# LTC3115_-_przetwornica_wiatrak.net
KiCad netlist of a schematic drawn in EAGLE
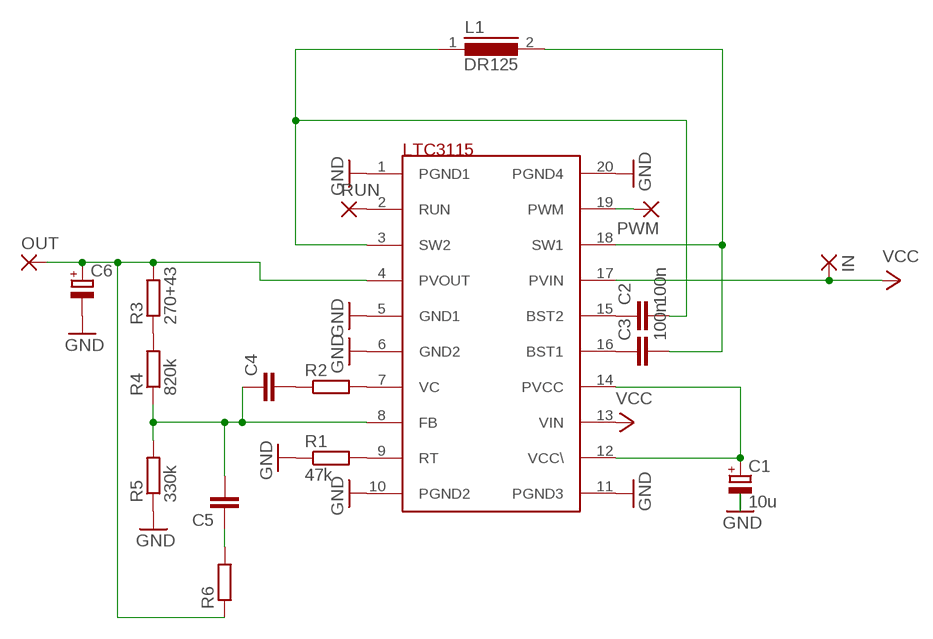
[diagram p0: schematic, sheet 1]

(export (version "E")
  (design (tool "Eeschema 10.0.6"))
  (components
    (comp (ref "C1")
      (value "10u")
      (footprint "eagle-import:E2,5-7")
      (libsource (lib "eagle-import") (part "CPOL-EUE2.5-7"))
    )
    (comp (ref "C2")
      (value "100n")
      (footprint "eagle-import:C0805")
      (libsource (lib "eagle-import") (part "C-EUC0805"))
    )
    (comp (ref "C3")
      (value "100n")
      (footprint "eagle-import:C0805")
      (libsource (lib "eagle-import") (part "C-EUC0805"))
    )
    (comp (ref "C4")
      (value "C-EUC0805")
      (footprint "eagle-import:C0805")
      (libsource (lib "eagle-import") (part "C-EUC0805"))
    )
    (comp (ref "C5")
      (value "C-EUC0805")
      (footprint "eagle-import:C0805")
      (libsource (lib "eagle-import") (part "C-EUC0805"))
    )
    (comp (ref "C6")
      (value "CPOL-EUE3.5-8")
      (footprint "eagle-import:E3,5-8")
      (libsource (lib "eagle-import") (part "CPOL-EUE3.5-8"))
    )
    (comp (ref "IN")
      (value "2,54/0,9")
      (footprint "eagle-import:2,54_0,9")
      (libsource (lib "eagle-import") (part "2,54/0,9"))
    )
    (comp (ref "L1")
      (value "DR125")
      (footprint "eagle-import:DR125")
      (libsource (lib "eagle-import") (part "DR125"))
    )
    (comp (ref "OUT")
      (value "2,54/0,9")
      (footprint "eagle-import:2,54_0,9")
      (libsource (lib "eagle-import") (part "2,54/0,9"))
    )
    (comp (ref "PWM")
      (value "2,54/0,9")
      (footprint "eagle-import:2,54_0,9")
      (libsource (lib "eagle-import") (part "2,54/0,9"))
    )
    (comp (ref "R1")
      (value "47k")
      (footprint "eagle-import:R0805")
      (libsource (lib "eagle-import") (part "R-EU_R0805"))
    )
    (comp (ref "R2")
      (value "R-EU_R0805")
      (footprint "eagle-import:R0805")
      (libsource (lib "eagle-import") (part "R-EU_R0805"))
    )
    (comp (ref "R3")
      (value "270+43")
      (footprint "eagle-import:R0805")
      (libsource (lib "eagle-import") (part "R-EU_R0805"))
    )
    (comp (ref "R4")
      (value "820k")
      (footprint "eagle-import:R0805")
      (libsource (lib "eagle-import") (part "R-EU_R0805"))
    )
    (comp (ref "R5")
      (value "330k")
      (footprint "eagle-import:R0805")
      (libsource (lib "eagle-import") (part "R-EU_R0805"))
    )
    (comp (ref "R6")
      (value "R-EU_R0805")
      (footprint "eagle-import:R0805")
      (libsource (lib "eagle-import") (part "R-EU_R0805"))
    )
    (comp (ref "RUN")
      (value "2,54/0,9")
      (footprint "eagle-import:2,54_0,9")
      (libsource (lib "eagle-import") (part "2,54/0,9"))
    )
    (comp (ref "U$1")
      (value "LTC3115")
      (footprint "eagle-import:TSSOP20")
      (libsource (lib "eagle-import") (part "LTC3115"))
    )
  )
  (nets
    (net (code "1") (name "GND") (class "Default")
      (node (ref "C1") (pin "-") (pinfunction "-_-") (pintype "passive"))
      (node (ref "C6") (pin "-") (pinfunction "-_-") (pintype "passive"))
      (node (ref "R1") (pin "1") (pinfunction "1_1") (pintype "passive"))
      (node (ref "R5") (pin "1") (pinfunction "1_1") (pintype "passive"))
      (node (ref "U$1") (pin "1") (pinfunction "PGND1_1") (pintype "bidirectional"))
      (node (ref "U$1") (pin "10") (pinfunction "PGND2_10") (pintype "bidirectional"))
      (node (ref "U$1") (pin "11") (pinfunction "PGND3_11") (pintype "bidirectional"))
      (node (ref "U$1") (pin "20") (pinfunction "PGND4_20") (pintype "bidirectional"))
      (node (ref "U$1") (pin "5") (pinfunction "GND1_5") (pintype "bidirectional"))
      (node (ref "U$1") (pin "6") (pinfunction "GND2_6") (pintype "bidirectional"))
    )
    (net (code "2") (name "Net-(C4-Pad2)") (class "Default")
      (node (ref "C4") (pin "2") (pinfunction "2_2") (pintype "passive"))
      (node (ref "R2") (pin "1") (pinfunction "1_1") (pintype "passive"))
    )
    (net (code "3") (name "Net-(C5-Pad1)") (class "Default")
      (node (ref "C5") (pin "1") (pinfunction "1_1") (pintype "passive"))
      (node (ref "R6") (pin "2") (pinfunction "2_2") (pintype "passive"))
    )
    (net (code "4") (name "Net-(OUT-P)") (class "Default")
      (node (ref "C6") (pin "+") (pinfunction "+_+") (pintype "passive"))
      (node (ref "OUT") (pin "1") (pinfunction "P_1") (pintype "passive"))
      (node (ref "R3") (pin "2") (pinfunction "2_2") (pintype "passive"))
      (node (ref "R6") (pin "1") (pinfunction "1_1") (pintype "passive"))
      (node (ref "U$1") (pin "4") (pinfunction "PVOUT_4") (pintype "bidirectional"))
    )
    (net (code "5") (name "Net-(PWM-P)") (class "Default")
      (node (ref "PWM") (pin "1") (pinfunction "P_1") (pintype "passive"))
      (node (ref "U$1") (pin "19") (pinfunction "PWM_19") (pintype "bidirectional"))
    )
    (net (code "6") (name "Net-(R3-Pad1)") (class "Default")
      (node (ref "R3") (pin "1") (pinfunction "1_1") (pintype "passive"))
      (node (ref "R4") (pin "2") (pinfunction "2_2") (pintype "passive"))
    )
    (net (code "7") (name "Net-(RUN-P)") (class "Default")
      (node (ref "RUN") (pin "1") (pinfunction "P_1") (pintype "passive"))
      (node (ref "U$1") (pin "2") (pinfunction "RUN_2") (pintype "bidirectional"))
    )
    (net (code "8") (name "Net-(U$1-BST1)") (class "Default")
      (node (ref "C3") (pin "1") (pinfunction "1_1") (pintype "passive"))
      (node (ref "U$1") (pin "16") (pinfunction "BST1_16") (pintype "bidirectional"))
    )
    (net (code "9") (name "Net-(U$1-BST2)") (class "Default")
      (node (ref "C2") (pin "1") (pinfunction "1_1") (pintype "passive"))
      (node (ref "U$1") (pin "15") (pinfunction "BST2_15") (pintype "bidirectional"))
    )
    (net (code "10") (name "Net-(U$1-FB)") (class "Default")
      (node (ref "C4") (pin "1") (pinfunction "1_1") (pintype "passive"))
      (node (ref "C5") (pin "2") (pinfunction "2_2") (pintype "passive"))
      (node (ref "R4") (pin "1") (pinfunction "1_1") (pintype "passive"))
      (node (ref "R5") (pin "2") (pinfunction "2_2") (pintype "passive"))
      (node (ref "U$1") (pin "8") (pinfunction "FB_8") (pintype "bidirectional"))
    )
    (net (code "11") (name "Net-(U$1-PVCC)") (class "Default")
      (node (ref "C1") (pin "+") (pinfunction "+_+") (pintype "passive"))
      (node (ref "U$1") (pin "12") (pinfunction "VCC\\_12") (pintype "bidirectional"))
      (node (ref "U$1") (pin "14") (pinfunction "PVCC_14") (pintype "bidirectional"))
    )
    (net (code "12") (name "Net-(U$1-RT)") (class "Default")
      (node (ref "R1") (pin "2") (pinfunction "2_2") (pintype "passive"))
      (node (ref "U$1") (pin "9") (pinfunction "RT_9") (pintype "bidirectional"))
    )
    (net (code "13") (name "Net-(U$1-SW1)") (class "Default")
      (node (ref "C3") (pin "2") (pinfunction "2_2") (pintype "passive"))
      (node (ref "L1") (pin "2") (pinfunction "2_2") (pintype "passive"))
      (node (ref "U$1") (pin "18") (pinfunction "SW1_18") (pintype "bidirectional"))
    )
    (net (code "14") (name "Net-(U$1-SW2)") (class "Default")
      (node (ref "C2") (pin "2") (pinfunction "2_2") (pintype "passive"))
      (node (ref "L1") (pin "1") (pinfunction "1_1") (pintype "passive"))
      (node (ref "U$1") (pin "3") (pinfunction "SW2_3") (pintype "bidirectional"))
    )
    (net (code "15") (name "Net-(U$1-VC)") (class "Default")
      (node (ref "R2") (pin "2") (pinfunction "2_2") (pintype "passive"))
      (node (ref "U$1") (pin "7") (pinfunction "VC_7") (pintype "bidirectional"))
    )
    (net (code "16") (name "VCC") (class "Default")
      (node (ref "IN") (pin "1") (pinfunction "P_1") (pintype "passive"))
      (node (ref "U$1") (pin "13") (pinfunction "VIN_13") (pintype "bidirectional"))
      (node (ref "U$1") (pin "17") (pinfunction "PVIN_17") (pintype "bidirectional"))
    )
  )
)
